# 2xparallelswitch_HALT.net
KiCad netlist of a schematic drawn in Altium Designer
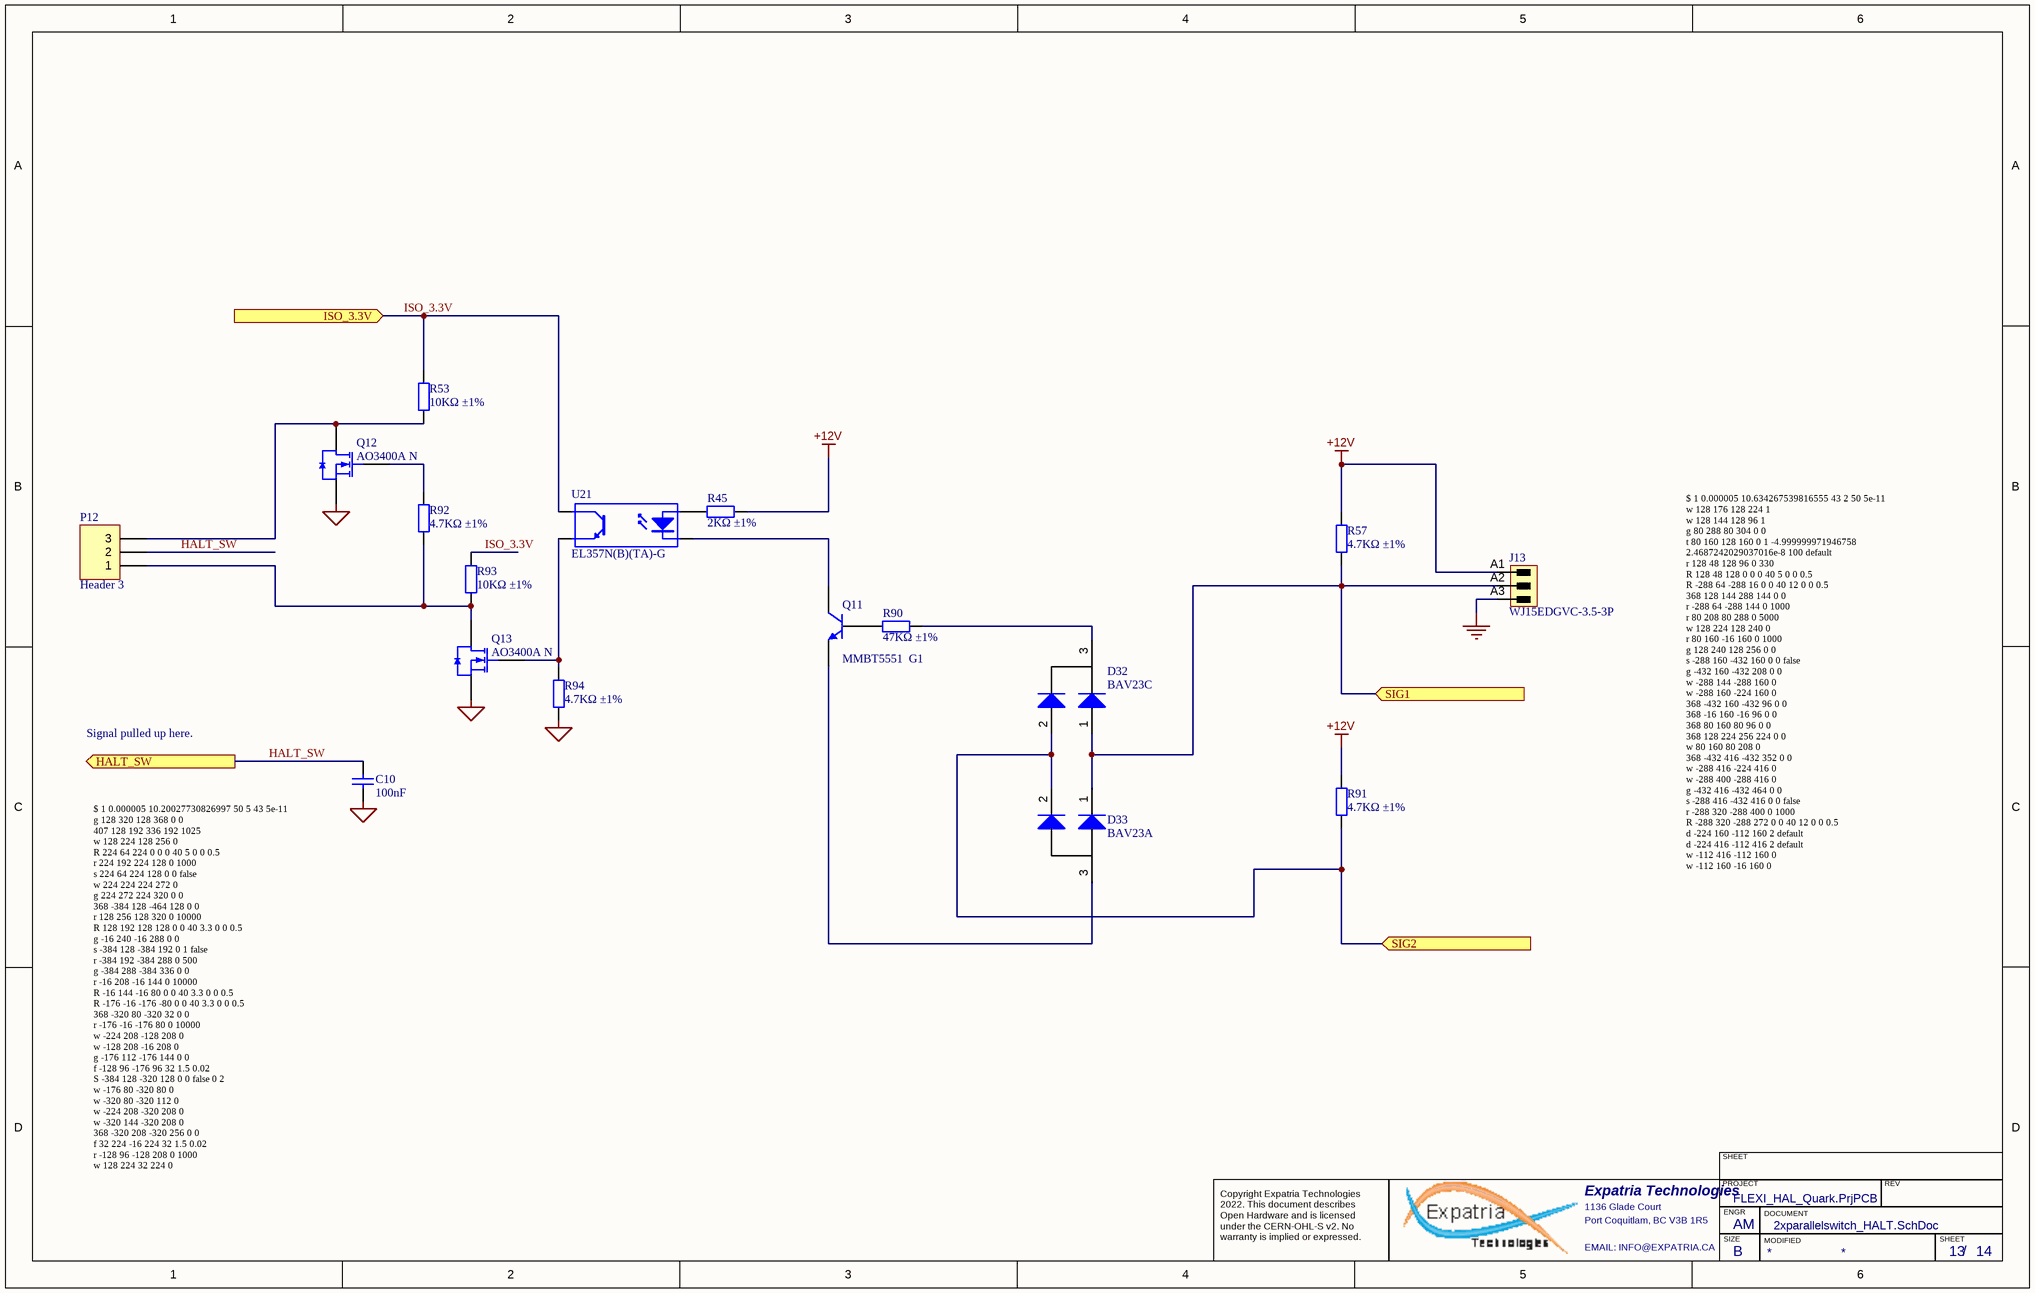
[diagram p0: 2xparallelswitch_HALT.SchDoc]

(export (version "E")
  (design (tool "Eeschema 10.0.6"))
  (components
    (comp (ref "C10")
      (value "100nF")
      (footprint "0603_C")
      (description "Chip capacitors")
      (fields (field (name "MANUFACTURER") "YAGEO") (field (name "PARTNUMBER") "CC0603KRX7R9BB104"))
      (libsource (lib "Cap") (part "0603 100nF (104) 10% 50V"))
    )
    (comp (ref "D32")
      (value "BAV23C")
      (footprint "SOT-23(SOT-23-3)")
      (libsource (lib "Diode") (part "SOT-23 BAV23C"))
    )
    (comp (ref "D33")
      (value "BAV23A")
      (footprint "SOT-23(SOT-23-3)")
      (libsource (lib "Diode") (part "SOT-23 BAV23A"))
    )
    (comp (ref "J13")
      (value "WJ15EDGVC-3.5-3P")
      (footprint "691321100003 - 3.5mm  3p")
      (fields (field (name "MANUFACTURER") "Weidmueller"))
      (libsource (lib "Universal_CNC_Breakout") (part "3.5mm Terminal Header 3p"))
    )
    (comp (ref "P12")
      (value "Header 3")
      (footprint "HDR1X3")
      (description "Header, 3-Pin")
      (fields (field (name "PUBLISHER") "Altium Limited"))
      (libsource (lib "Miscellaneous Connectors") (part "Header 3"))
    )
    (comp (ref "Q11")
      (value "MMBT5551  G1")
      (footprint "SOT-23(SOT-23-3)")
      (description "三极管")
      (libsource (lib "Transistor_NPN") (part "SOT-23 MMBT5551  G1"))
    )
    (comp (ref "Q12")
      (value "AO3400A N")
      (footprint "SOT-23-3L")
      (description "MOS(场效应管)")
      (libsource (lib "MOS") (part "AO3400A N道沟 X0YV1T SOT-23"))
    )
    (comp (ref "Q13")
      (value "AO3400A N")
      (footprint "SOT-23-3L")
      (description "MOS(场效应管)")
      (libsource (lib "MOS") (part "AO3400A N道沟 X0YV1T SOT-23"))
    )
    (comp (ref "R45")
      (value "2KΩ ±1%")
      (footprint "0603_R")
      (description "Chip resistor")
      (fields (field (name "MANUFACTURER") "Uniroyal Elec") (field (name "PARTNUMBER") "0603WAF2001T5E"))
      (libsource (lib "RES") (part "0603 2K (2001) 1%"))
    )
    (comp (ref "R53")
      (value "10KΩ ±1%")
      (footprint "0603_R")
      (description "Chip resistor")
      (fields (field (name "MANUFACTURER") "Uniroyal Elec") (field (name "PARTNUMBER") "0603WAF1002T5E"))
      (libsource (lib "RES") (part "0603 10K (1002) 1%"))
    )
    (comp (ref "R57")
      (value "4.7KΩ ±1%")
      (footprint "0603_R")
      (description "Chip resistor")
      (fields (field (name "MANUFACTURER") "Uniroyal Elec") (field (name "PARTNUMBER") "0603WAF4701T5E"))
      (libsource (lib "RES") (part "0603 4.7K (4701) 1%"))
    )
    (comp (ref "R90")
      (value "47KΩ ±1%")
      (footprint "0603_R")
      (description "Chip resistor")
      (fields (field (name "MANUFACTURER") "Uniroyal Elec") (field (name "PARTNUMBER") "0603WAF4702T5E"))
      (libsource (lib "RES") (part "0603 47K (4702) 1%"))
    )
    (comp (ref "R91")
      (value "4.7KΩ ±1%")
      (footprint "0603_R")
      (description "Chip resistor")
      (fields (field (name "MANUFACTURER") "Uniroyal Elec") (field (name "PARTNUMBER") "0603WAF4701T5E"))
      (libsource (lib "RES") (part "0603 4.7K (4701) 1%"))
    )
    (comp (ref "R92")
      (value "4.7KΩ ±1%")
      (footprint "0603_R")
      (description "Chip resistor")
      (fields (field (name "MANUFACTURER") "Uniroyal Elec") (field (name "PARTNUMBER") "0603WAF4701T5E"))
      (libsource (lib "RES") (part "0603 4.7K (4701) 1%"))
    )
    (comp (ref "R93")
      (value "10KΩ ±1%")
      (footprint "0603_R")
      (description "Chip resistor")
      (fields (field (name "MANUFACTURER") "Uniroyal Elec") (field (name "PARTNUMBER") "0603WAF1002T5E"))
      (libsource (lib "RES") (part "0603 10K (1002) 1%"))
    )
    (comp (ref "R94")
      (value "4.7KΩ ±1%")
      (footprint "0603_R")
      (description "Chip resistor")
      (fields (field (name "MANUFACTURER") "Uniroyal Elec") (field (name "PARTNUMBER") "0603WAF4701T5E"))
      (libsource (lib "RES") (part "0603 4.7K (4701) 1%"))
    )
    (comp (ref "U21")
      (value "EL357N(B)(TA)-G")
      (footprint "Miscellaneous Devices LC:SOP-4_P2.54")
      (description "贴片光耦")
      (libsource (lib "IC") (part "EL357N(B)(TA)-G_[C6649]"))
    )
  )
  (nets
    (net (code "1") (name "+12V") (class "Default")
      (node (ref "J13") (pin "A1") (pinfunction "A1_A1") (pintype "passive"))
      (node (ref "R45") (pin "2") (pinfunction "2_2") (pintype "passive"))
      (node (ref "R57") (pin "2") (pinfunction "2_2") (pintype "passive"))
      (node (ref "R91") (pin "2") (pinfunction "2_2") (pintype "passive"))
    )
    (net (code "2") (name "/HALT_SW") (class "Default")
      (node (ref "C10") (pin "2") (pinfunction "2_2") (pintype "passive"))
      (node (ref "P12") (pin "2") (pinfunction "2_2") (pintype "passive"))
    )
    (net (code "3") (name "/ISO_3.3V") (class "Default")
      (node (ref "R53") (pin "2") (pinfunction "2_2") (pintype "passive"))
      (node (ref "R93") (pin "2") (pinfunction "2_2") (pintype "passive"))
      (node (ref "U21") (pin "4") (pinfunction "C_4") (pintype "passive"))
    )
    (net (code "4") (name "/SIG1") (class "Default")
      (node (ref "D32") (pin "1") (pinfunction "A_1") (pintype "passive"))
      (node (ref "D33") (pin "1") (pinfunction "K_1") (pintype "passive"))
      (node (ref "J13") (pin "A2") (pinfunction "A2_A2") (pintype "passive"))
      (node (ref "R57") (pin "1") (pinfunction "1_1") (pintype "passive"))
    )
    (net (code "5") (name "/SIG2") (class "Default")
      (node (ref "D32") (pin "2") (pinfunction "A_2") (pintype "passive"))
      (node (ref "D33") (pin "2") (pinfunction "K_2") (pintype "passive"))
      (node (ref "R91") (pin "1") (pinfunction "1_1") (pintype "passive"))
    )
    (net (code "6") (name "GND") (class "Default")
      (node (ref "J13") (pin "A3") (pinfunction "A3_A3") (pintype "passive"))
    )
    (net (code "7") (name "MCU_GND") (class "Default")
      (node (ref "C10") (pin "1") (pinfunction "1_1") (pintype "passive"))
      (node (ref "Q12") (pin "2") (pinfunction "S_2") (pintype "passive"))
      (node (ref "Q13") (pin "2") (pinfunction "S_2") (pintype "passive"))
      (node (ref "R94") (pin "1") (pinfunction "1_1") (pintype "passive"))
    )
    (net (code "8") (name "Net-(D32-K)") (class "Default")
      (node (ref "D32") (pin "3") (pinfunction "K_3") (pintype "passive"))
      (node (ref "R90") (pin "1") (pinfunction "1_1") (pintype "passive"))
    )
    (net (code "9") (name "Net-(D33-A)") (class "Default")
      (node (ref "D33") (pin "3") (pinfunction "A_3") (pintype "passive"))
      (node (ref "Q11") (pin "2") (pinfunction "E_2") (pintype "passive"))
    )
    (net (code "10") (name "Net-(Q11-B)") (class "Default")
      (node (ref "Q11") (pin "1") (pinfunction "B_1") (pintype "passive"))
      (node (ref "R90") (pin "2") (pinfunction "2_2") (pintype "passive"))
    )
    (net (code "11") (name "Net-(Q11-C)") (class "Default")
      (node (ref "Q11") (pin "3") (pinfunction "C_3") (pintype "passive"))
      (node (ref "U21") (pin "2") (pinfunction "K_2") (pintype "passive"))
    )
    (net (code "12") (name "Net-(Q12-D)") (class "Default")
      (node (ref "P12") (pin "3") (pinfunction "3_3") (pintype "passive"))
      (node (ref "Q12") (pin "3") (pinfunction "D_3") (pintype "passive"))
      (node (ref "R53") (pin "1") (pinfunction "1_1") (pintype "passive"))
    )
    (net (code "13") (name "Net-(Q12-G)") (class "Default")
      (node (ref "Q12") (pin "1") (pinfunction "G_1") (pintype "passive"))
      (node (ref "R92") (pin "2") (pinfunction "2_2") (pintype "passive"))
    )
    (net (code "14") (name "Net-(Q13-D)") (class "Default")
      (node (ref "P12") (pin "1") (pinfunction "1_1") (pintype "passive"))
      (node (ref "Q13") (pin "3") (pinfunction "D_3") (pintype "passive"))
      (node (ref "R92") (pin "1") (pinfunction "1_1") (pintype "passive"))
      (node (ref "R93") (pin "1") (pinfunction "1_1") (pintype "passive"))
    )
    (net (code "15") (name "Net-(Q13-G)") (class "Default")
      (node (ref "Q13") (pin "1") (pinfunction "G_1") (pintype "passive"))
      (node (ref "R94") (pin "2") (pinfunction "2_2") (pintype "passive"))
      (node (ref "U21") (pin "3") (pinfunction "E_3") (pintype "passive"))
    )
    (net (code "16") (name "Net-(U21-A)") (class "Default")
      (node (ref "R45") (pin "1") (pinfunction "1_1") (pintype "passive"))
      (node (ref "U21") (pin "1") (pinfunction "A_1") (pintype "passive"))
    )
  )
)
